# Power.net
KiCad netlist of a schematic drawn in Altium Designer
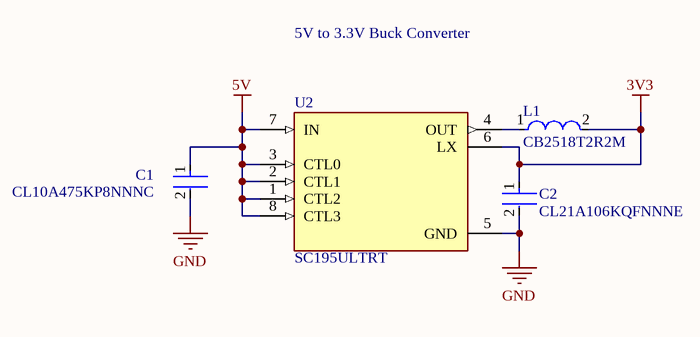
[diagram p0: Power.SchDoc]

(export (version "E")
  (design (tool "Eeschema 10.0.6"))
  (components
    (comp (ref "C1")
      (value "CL10A475KP8NNNC")
      (footprint "FP-CL10-IPC_C")
      (description "Cap Ceramic 4.7uF 10V X5R ±10% Pad SMD 0603 +85°C T/R")
      (fields (field (name "TOLERANCE") "10%"))
      (libsource (lib "Altium Content Vault") (part "b4654b650e69147ec39a6b967a45e02"))
    )
    (comp (ref "C2")
      (value "CL21A106KQFNNNE")
      (footprint "FP-CL21-IPC_A")
      (description "CL21 Series 0805 10uF 6.3V ±10% Tolerance X5R Multilayer Ceramic Chip Capacitor")
      (fields (field (name "TOLERANCE") "10%"))
      (libsource (lib "Altium Content Vault") (part "b4654b650e69147ec39a6b967a45e02"))
    )
    (comp (ref "L1")
      (value "CB2518T2R2M")
      (footprint "FP-CB2518-IPC_C")
      (description "SMD Inductors 2.2uH ±20% 1.3A 0.117Ω 1007")
      (fields (field (name "TOLERANCE") "20%"))
      (libsource (lib "Altium Content Vault") (part "725321dda6339637d4d059423bc1c3c"))
    )
    (comp (ref "U2")
      (value "SC195ULTRT")
      (footprint "SC195ULTRT:QFN40P150X150X60-8N")
      (description "Buck Switching Regulator IC Positive Programmable 0.8V 1 Output 500mA 8-UFQFN")
      (fields (field (name "MF") "{'manufacturer': u'Semtech Corporation'}"))
      (libsource (lib "*") (part "SC195ULTRT"))
    )
  )
  (nets
    (net (code "1") (name "3V3") (class "Default")
      (node (ref "C2") (pin "1") (pinfunction "1_1") (pintype "passive"))
      (node (ref "L1") (pin "2") (pinfunction "2_2") (pintype "passive"))
      (node (ref "U2") (pin "6") (pinfunction "LX_6") (pintype "passive"))
    )
    (net (code "2") (name "5V") (class "Default")
      (node (ref "C1") (pin "1") (pinfunction "1_1") (pintype "passive"))
      (node (ref "U2") (pin "1") (pinfunction "CTL2_1") (pintype "input"))
      (node (ref "U2") (pin "2") (pinfunction "CTL1_2") (pintype "input"))
      (node (ref "U2") (pin "3") (pinfunction "CTL0_3") (pintype "input"))
      (node (ref "U2") (pin "7") (pinfunction "IN_7") (pintype "input"))
      (node (ref "U2") (pin "8") (pinfunction "CTL3_8") (pintype "input"))
    )
    (net (code "3") (name "GND") (class "Default")
      (node (ref "C1") (pin "2") (pinfunction "2_2") (pintype "passive"))
      (node (ref "C2") (pin "2") (pinfunction "2_2") (pintype "passive"))
      (node (ref "U2") (pin "5") (pinfunction "GND_5") (pintype "power_in"))
    )
    (net (code "4") (name "Net-(U2-OUT)") (class "Default")
      (node (ref "L1") (pin "1") (pinfunction "1_1") (pintype "passive"))
      (node (ref "U2") (pin "4") (pinfunction "OUT_4") (pintype "output"))
    )
  )
)
